# AthenaAmpli.net
KiCad netlist of a schematic drawn in EAGLE
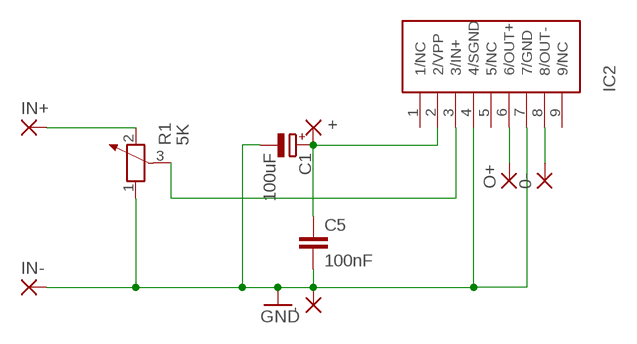
[diagram p0: schematic, sheet 1]

(export (version "E")
  (design (tool "Eeschema 10.0.6"))
  (components
    (comp (ref "+")
      (value "WIREPAD3,17/1,2")
      (footprint "eagle-import:3,17_1,2")
      (libsource (lib "eagle-import") (part "WIREPAD3,17/1,2"))
    )
    (comp (ref "-")
      (value "WIREPAD3,17/1,2")
      (footprint "eagle-import:3,17_1,2")
      (libsource (lib "eagle-import") (part "WIREPAD3,17/1,2"))
    )
    (comp (ref "0-")
      (value "WIREPAD3,17/1,2")
      (footprint "eagle-import:3,17_1,2")
      (libsource (lib "eagle-import") (part "WIREPAD3,17/1,2"))
    )
    (comp (ref "C1")
      (value "100uF")
      (footprint "eagle-import:E3,5-8")
      (libsource (lib "eagle-import") (part "CPOL-EUE3.5-8"))
    )
    (comp (ref "C5")
      (value "100nF")
      (footprint "eagle-import:C050-024X044")
      (libsource (lib "eagle-import") (part "C-EU050-024X044"))
    )
    (comp (ref "IC2")
      (value "TDA7056")
      (footprint "eagle-import:SOT110-1")
      (libsource (lib "eagle-import") (part "TDA7056"))
    )
    (comp (ref "IN+")
      (value "WIREPAD3,17/1,2")
      (footprint "eagle-import:3,17_1,2")
      (libsource (lib "eagle-import") (part "WIREPAD3,17/1,2"))
    )
    (comp (ref "IN-")
      (value "WIREPAD3,17/1,2")
      (footprint "eagle-import:3,17_1,2")
      (libsource (lib "eagle-import") (part "WIREPAD3,17/1,2"))
    )
    (comp (ref "O+")
      (value "WIREPAD3,17/1,2")
      (footprint "eagle-import:3,17_1,2")
      (libsource (lib "eagle-import") (part "WIREPAD3,17/1,2"))
    )
    (comp (ref "R1")
      (value "5K")
      (footprint "eagle-import:PT-10S")
      (libsource (lib "eagle-import") (part "POTENTIOMETER_PT-10S"))
    )
  )
  (nets
    (net (code "1") (name "GND") (class "Default")
      (node (ref "-") (pin "1") (pinfunction "P_1") (pintype "passive"))
      (node (ref "C1") (pin "-") (pinfunction "-_-") (pintype "passive"))
      (node (ref "C5") (pin "2") (pinfunction "2_2") (pintype "passive"))
      (node (ref "IC2") (pin "4") (pinfunction "4/SGND_4") (pintype "power_in"))
      (node (ref "IC2") (pin "7") (pinfunction "7/GND_7") (pintype "power_in"))
      (node (ref "IN-") (pin "1") (pinfunction "P_1") (pintype "passive"))
      (node (ref "R1") (pin "1") (pinfunction "1_1") (pintype "passive"))
    )
    (net (code "2") (name "Net-(+-P)") (class "Default")
      (node (ref "+") (pin "1") (pinfunction "P_1") (pintype "passive"))
      (node (ref "C1") (pin "+") (pinfunction "+_+") (pintype "passive"))
      (node (ref "C5") (pin "1") (pinfunction "1_1") (pintype "passive"))
      (node (ref "IC2") (pin "2") (pinfunction "2/VPP_2") (pintype "power_in"))
    )
    (net (code "3") (name "Net-(0--P)") (class "Default")
      (node (ref "0-") (pin "1") (pinfunction "P_1") (pintype "passive"))
      (node (ref "IC2") (pin "8") (pinfunction "8/OUT-_8") (pintype "output"))
    )
    (net (code "4") (name "Net-(IC2-3{slash}IN+)") (class "Default")
      (node (ref "IC2") (pin "3") (pinfunction "3/IN+_3") (pintype "input"))
      (node (ref "R1") (pin "3") (pinfunction "3_3") (pintype "passive"))
    )
    (net (code "5") (name "Net-(IC2-6{slash}OUT+)") (class "Default")
      (node (ref "IC2") (pin "6") (pinfunction "6/OUT+_6") (pintype "output"))
      (node (ref "O+") (pin "1") (pinfunction "P_1") (pintype "passive"))
    )
    (net (code "6") (name "Net-(IN+-P)") (class "Default")
      (node (ref "IN+") (pin "1") (pinfunction "P_1") (pintype "passive"))
      (node (ref "R1") (pin "2") (pinfunction "2_2") (pintype "passive"))
    )
    (net (code "7") (name "unconnected-(IC2-1{slash}NC-Pad1)") (class "Default")
      (node (ref "IC2") (pin "1") (pinfunction "1/NC_1") (pintype "no_connect"))
    )
    (net (code "8") (name "unconnected-(IC2-5{slash}NC-Pad5)") (class "Default")
      (node (ref "IC2") (pin "5") (pinfunction "5/NC_5") (pintype "no_connect"))
    )
    (net (code "9") (name "unconnected-(IC2-9{slash}NC-Pad9)") (class "Default")
      (node (ref "IC2") (pin "9") (pinfunction "9/NC_9") (pintype "no_connect"))
    )
  )
)
